# Rpi_power_and_fan.net
KiCad netlist of a schematic drawn in EasyEDA Pro
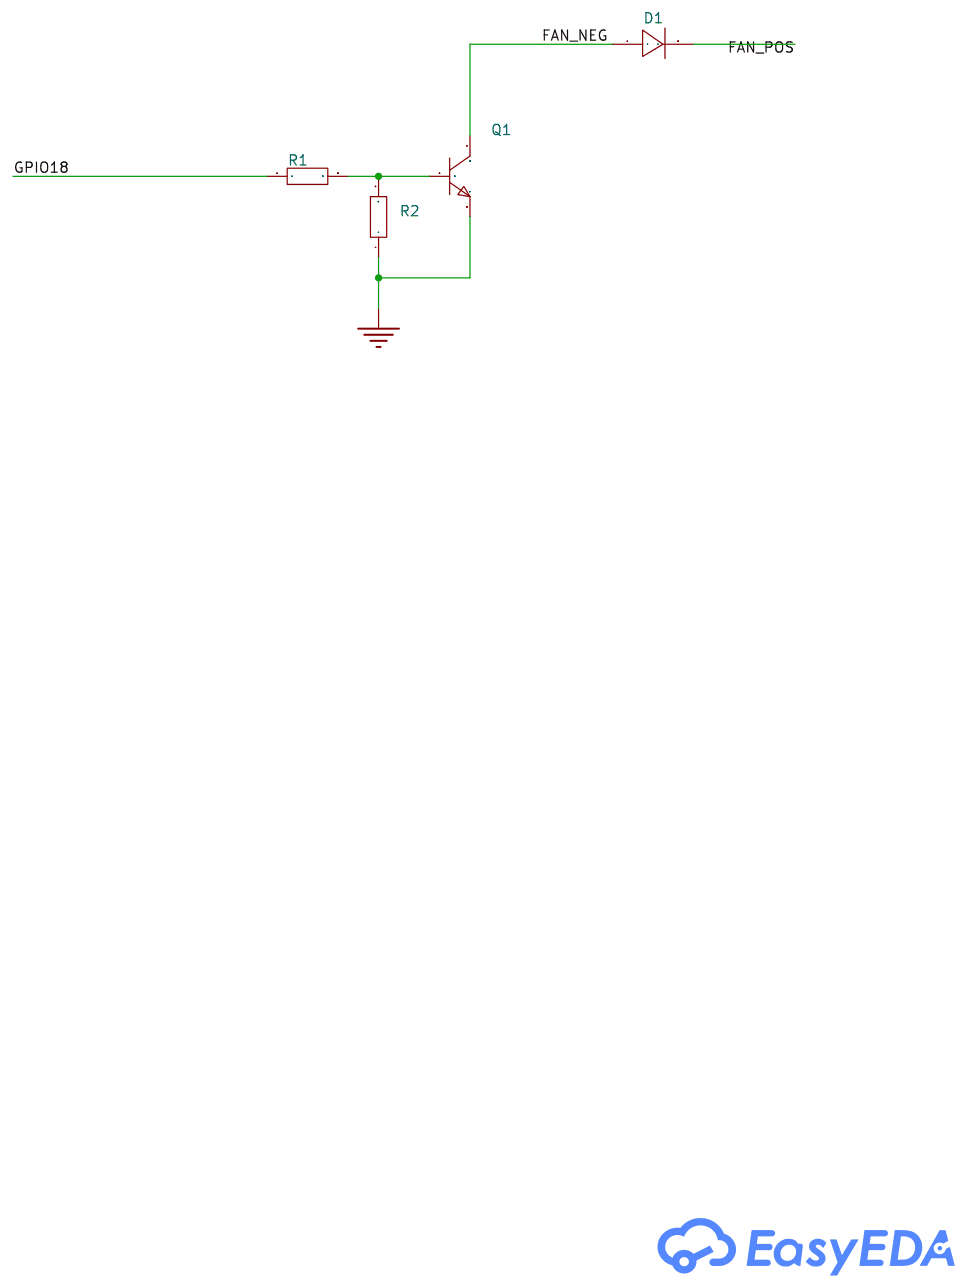
[diagram p0: schematic sheet]

(export (version "E")
  (design (tool "Eeschema 10.0.6"))
  (components
    (comp (ref "D1")
      (value "~")
      (footprint "easyedapro:DO-41_BD2.8-L4.2-P8.00-D0.7-FD")
      (fields (field (name "Manufacturer Part") "UF4007") (field (name "Manufacturer") "onsemi(安森美)"))
      (libsource (lib "easyedapro") (part "UF4007_C232764"))
    )
    (comp (ref "Q1")
      (value "~")
      (footprint "easyedapro:TO-92-3_L4.8-W3.7-P2.54-L")
      (fields (field (name "Manufacturer Part") "BC547BTA") (field (name "Manufacturer") "onsemi(安森美)"))
      (libsource (lib "easyedapro") (part "BC547BTA"))
    )
    (comp (ref "R1")
      (value "2.4kΩ")
      (footprint "easyedapro:R0402")
      (fields (field (name "Manufacturer Part") "RC0402FR-072K4L") (field (name "Manufacturer") "YAGEO(国巨)"))
      (libsource (lib "easyedapro") (part "RC0402FR-072K4L"))
    )
    (comp (ref "R2")
      (value "10kΩ")
      (footprint "easyedapro:R0805")
      (fields
        (field (name "Manufacturer Part") "RMCF0805FT10K0")
        (field (name "Manufacturer") "SEI(Stackpole Electronics Inc.)")
      )
      (libsource (lib "easyedapro") (part "RMCF0805FT10K0"))
    )
  )
  (nets
    (net (code "1") (name "/FAN_NEG") (class "Default")
      (node (ref "D1") (pin "1") (pinfunction "A_1") (pintype "input"))
      (node (ref "Q1") (pin "1") (pinfunction "C_1") (pintype "input"))
    )
    (net (code "2") (name "/FAN_POS") (class "Default")
      (node (ref "D1") (pin "2") (pinfunction "K_2") (pintype "input"))
    )
    (net (code "3") (name "/GPIO18") (class "Default")
      (node (ref "R1") (pin "1") (pinfunction "1_1") (pintype "input"))
    )
    (net (code "4") (name "GND") (class "Default")
      (node (ref "Q1") (pin "3") (pinfunction "E_3") (pintype "input"))
      (node (ref "R2") (pin "1") (pinfunction "1_1") (pintype "input"))
    )
    (net (code "5") (name "Net-(Q1-B)") (class "Default")
      (node (ref "Q1") (pin "2") (pinfunction "B_2") (pintype "input"))
      (node (ref "R1") (pin "2") (pinfunction "2_2") (pintype "input"))
      (node (ref "R2") (pin "2") (pinfunction "2_2") (pintype "input"))
    )
  )
)
